# uController.net
KiCad netlist of a schematic drawn in Altium Designer
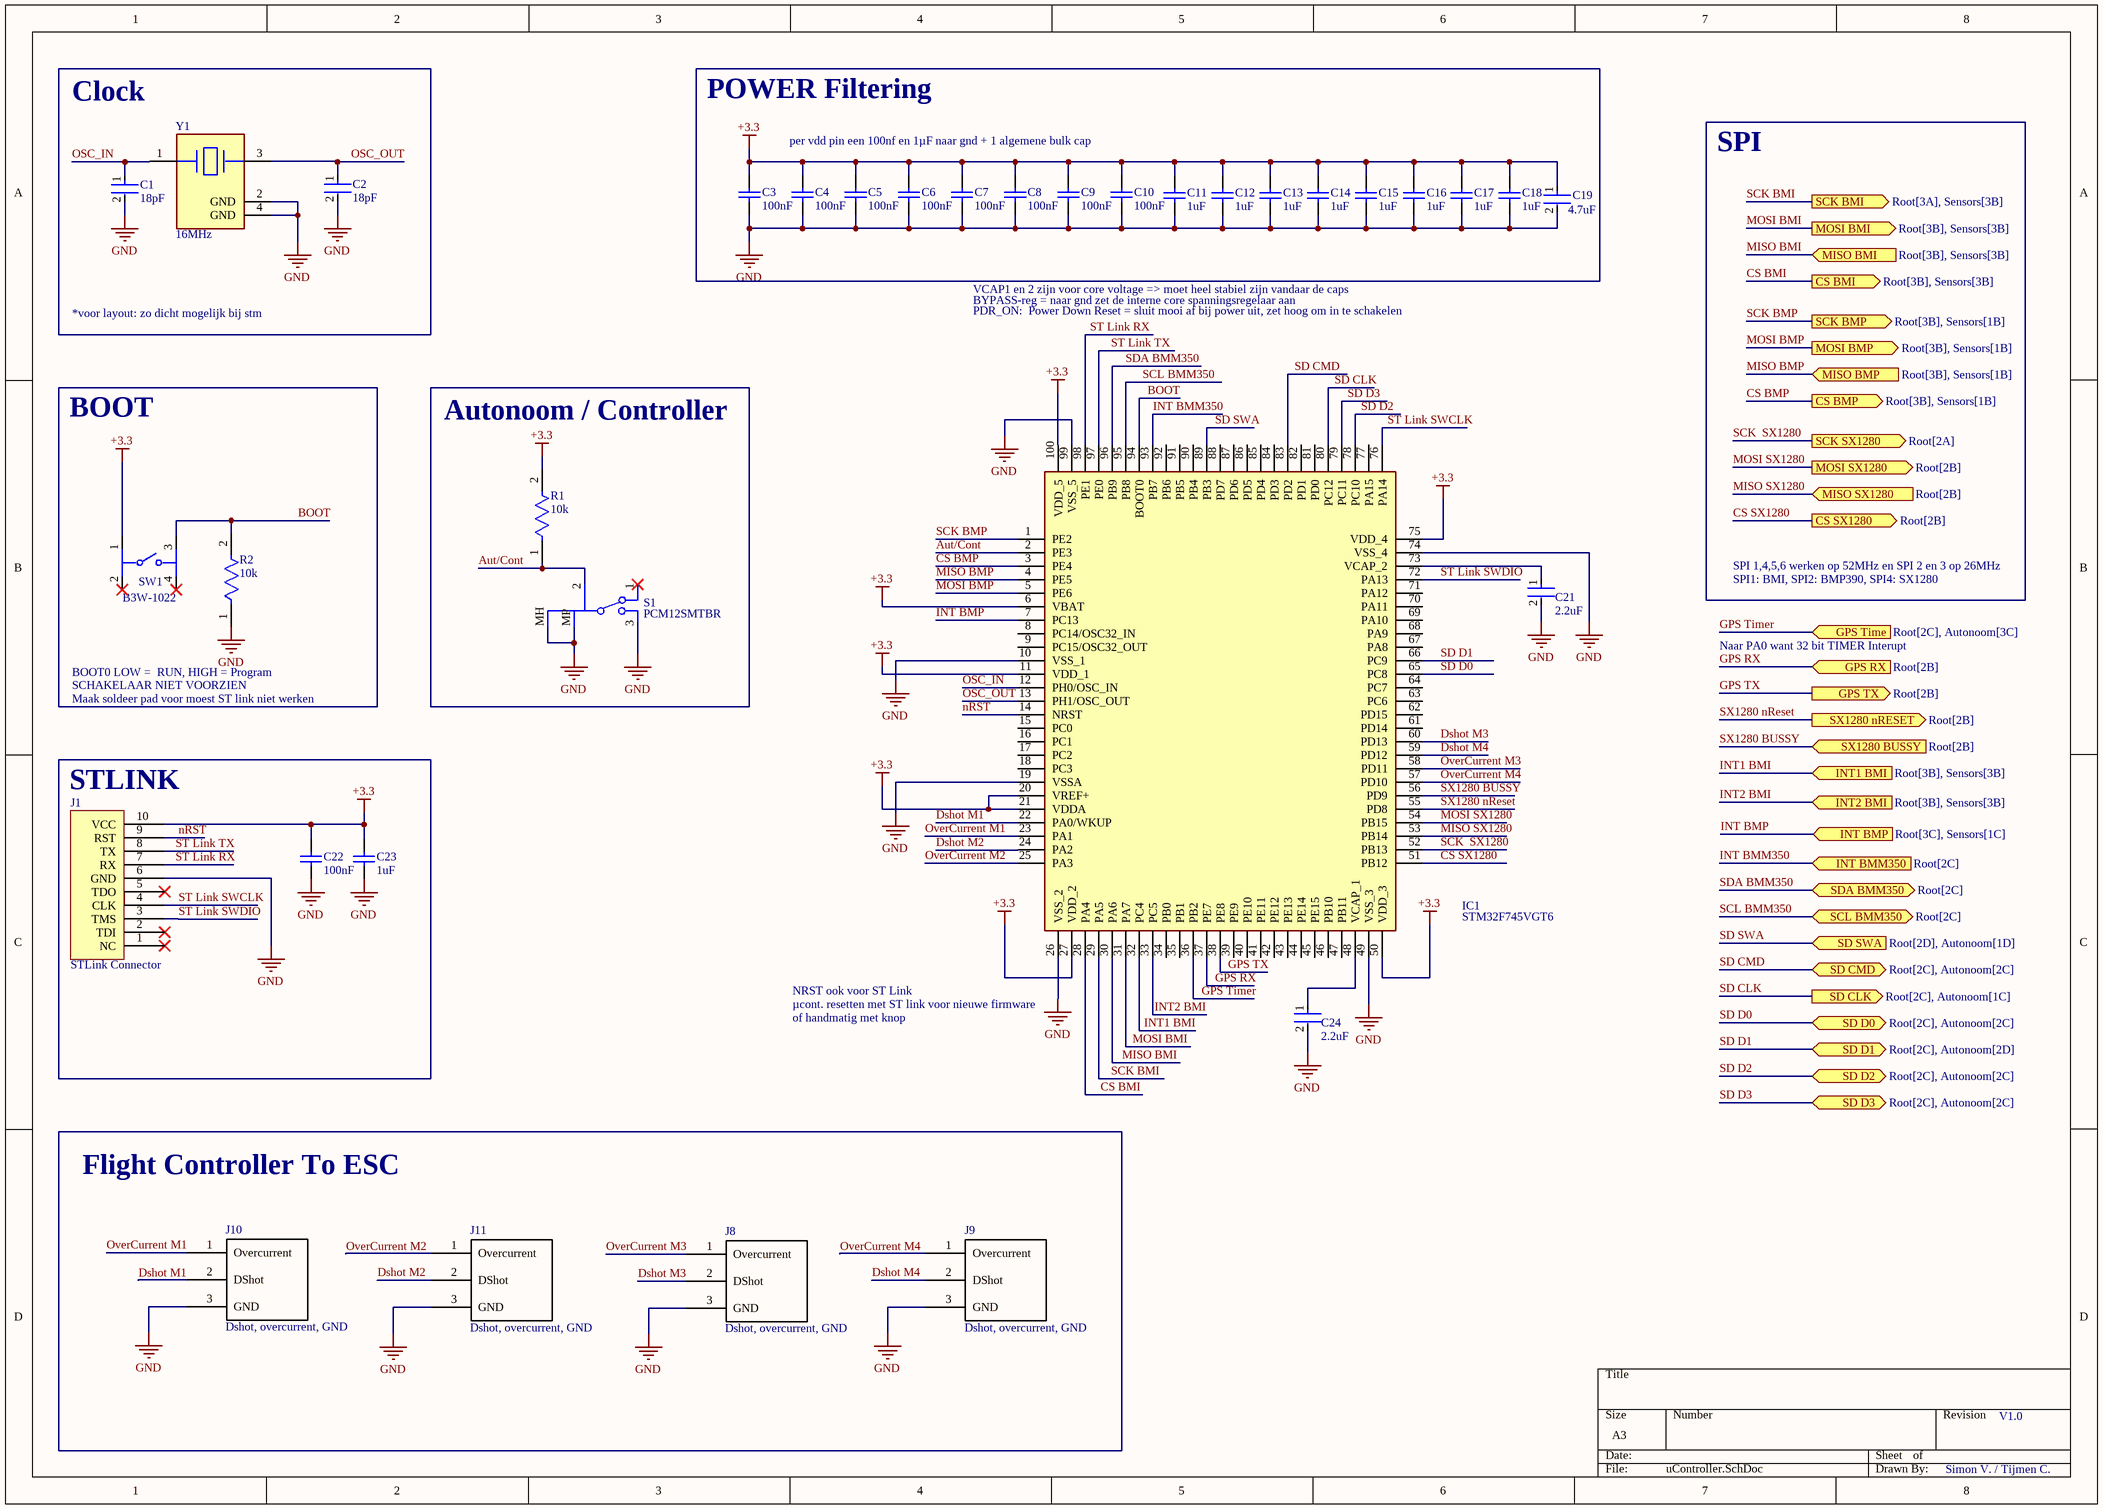
[diagram p0: uController.SchDoc]

(export (version "E")
  (design (tool "Eeschema 10.0.6"))
  (components
    (comp (ref "C1")
      (value "18pF")
      (footprint "FP-C0603C-CF-MFG")
      (description "C0603 18 pF C0G 30ppm/°C 1.00% 50 V")
      (fields
        (field (name "MANUFACTURER") "KEMET")
        (field (name "MANUFACTURER PART NUMBER") "C0603C180F5GACAUTO")
      )
      (libsource (lib "Altium Content Vault") (part "b4654b650e69147ec39a6b967a45e02"))
    )
    (comp (ref "C2")
      (value "18pF")
      (footprint "FP-C0603C-CF-MFG")
      (description "C0603 18 pF C0G 30ppm/°C 1.00% 50 V")
      (fields
        (field (name "MANUFACTURER") "KEMET")
        (field (name "MANUFACTURER PART NUMBER") "C0603C180F5GACAUTO")
      )
      (libsource (lib "Altium Content Vault") (part "b4654b650e69147ec39a6b967a45e02"))
    )
    (comp (ref "C3")
      (value "100nF")
      (footprint "CAPC1608X92X38ML15T08")
      (fields (field (name "PART NUMBER") "VJ0603Y104MXXAC") (field (name "MANUFACTURER") "Vitramon"))
      (libsource (lib "Altium Content Vault") (part "CAP"))
    )
    (comp (ref "C4")
      (value "100nF")
      (footprint "CAPC1608X92X38ML15T08")
      (fields (field (name "PART NUMBER") "VJ0603Y104MXXAC") (field (name "MANUFACTURER") "Vitramon"))
      (libsource (lib "Altium Content Vault") (part "CAP"))
    )
    (comp (ref "C5")
      (value "100nF")
      (footprint "CAPC1608X92X38ML15T08")
      (fields (field (name "PART NUMBER") "VJ0603Y104MXXAC") (field (name "MANUFACTURER") "Vitramon"))
      (libsource (lib "Altium Content Vault") (part "CAP"))
    )
    (comp (ref "C6")
      (value "100nF")
      (footprint "CAPC1608X92X38ML15T08")
      (fields (field (name "PART NUMBER") "VJ0603Y104MXXAC") (field (name "MANUFACTURER") "Vitramon"))
      (libsource (lib "Altium Content Vault") (part "CAP"))
    )
    (comp (ref "C7")
      (value "100nF")
      (footprint "CAPC1608X92X38ML15T08")
      (fields (field (name "PART NUMBER") "VJ0603Y104MXXAC") (field (name "MANUFACTURER") "Vitramon"))
      (libsource (lib "Altium Content Vault") (part "CAP"))
    )
    (comp (ref "C8")
      (value "100nF")
      (footprint "CAPC1608X92X38ML15T08")
      (fields (field (name "PART NUMBER") "VJ0603Y104MXXAC") (field (name "MANUFACTURER") "Vitramon"))
      (libsource (lib "Altium Content Vault") (part "CAP"))
    )
    (comp (ref "C9")
      (value "100nF")
      (footprint "CAPC1608X92X38ML15T08")
      (fields (field (name "PART NUMBER") "VJ0603Y104MXXAC") (field (name "MANUFACTURER") "Vitramon"))
      (libsource (lib "Altium Content Vault") (part "CAP"))
    )
    (comp (ref "C10")
      (value "100nF")
      (footprint "CAPC1608X92X38ML15T08")
      (fields (field (name "PART NUMBER") "VJ0603Y104MXXAC") (field (name "MANUFACTURER") "Vitramon"))
      (libsource (lib "Altium Content Vault") (part "CAP"))
    )
    (comp (ref "C11")
      (value "1uF")
      (footprint "CAPC1608X90X35NL15T15")
      (fields
        (field (name "PART NUMBER") "0603YD105MAT2A")
        (field (name "MANUFACTURER") "AVX Interconnect / Elco")
      )
      (libsource (lib "Altium Content Vault") (part "CAP"))
    )
    (comp (ref "C12")
      (value "1uF")
      (footprint "CAPC1608X90X35NL15T15")
      (fields
        (field (name "PART NUMBER") "0603YD105MAT2A")
        (field (name "MANUFACTURER") "AVX Interconnect / Elco")
      )
      (libsource (lib "Altium Content Vault") (part "CAP"))
    )
    (comp (ref "C13")
      (value "1uF")
      (footprint "CAPC1608X90X35NL15T15")
      (fields
        (field (name "PART NUMBER") "0603YD105MAT2A")
        (field (name "MANUFACTURER") "AVX Interconnect / Elco")
      )
      (libsource (lib "Altium Content Vault") (part "CAP"))
    )
    (comp (ref "C14")
      (value "1uF")
      (footprint "CAPC1608X90X35NL15T15")
      (fields
        (field (name "PART NUMBER") "0603YD105MAT2A")
        (field (name "MANUFACTURER") "AVX Interconnect / Elco")
      )
      (libsource (lib "Altium Content Vault") (part "CAP"))
    )
    (comp (ref "C15")
      (value "1uF")
      (footprint "CAPC1608X90X35NL15T15")
      (fields
        (field (name "PART NUMBER") "0603YD105MAT2A")
        (field (name "MANUFACTURER") "AVX Interconnect / Elco")
      )
      (libsource (lib "Altium Content Vault") (part "CAP"))
    )
    (comp (ref "C16")
      (value "1uF")
      (footprint "CAPC1608X90X35NL15T15")
      (fields
        (field (name "PART NUMBER") "0603YD105MAT2A")
        (field (name "MANUFACTURER") "AVX Interconnect / Elco")
      )
      (libsource (lib "Altium Content Vault") (part "CAP"))
    )
    (comp (ref "C17")
      (value "1uF")
      (footprint "CAPC1608X90X35NL15T15")
      (fields
        (field (name "PART NUMBER") "0603YD105MAT2A")
        (field (name "MANUFACTURER") "AVX Interconnect / Elco")
      )
      (libsource (lib "Altium Content Vault") (part "CAP"))
    )
    (comp (ref "C18")
      (value "1uF")
      (footprint "CAPC1608X90X35NL15T15")
      (fields
        (field (name "PART NUMBER") "0603YD105MAT2A")
        (field (name "MANUFACTURER") "AVX Interconnect / Elco")
      )
      (libsource (lib "Altium Content Vault") (part "CAP"))
    )
    (comp (ref "C19")
      (value "4.7uF")
      (footprint "FP-CC0603-DC-MFG")
      (description "CAP CER 4.7UF 6.3V X7R 0603")
      (fields (field (name "TOLERANCE") "20%"))
      (libsource (lib "Altium Content Vault") (part "11868f565c42a9108669ba33697ecf6"))
    )
    (comp (ref "C21")
      (value "2.2uF")
      (footprint "FP-CC0603-DA-MFG")
      (description "CC0603 2.2 uF X5R 10.00% 16 V")
      (fields
        (field (name "MANUFACTURER") "YAGEO")
        (field (name "MANUFACTURER PART NUMBER") "CC0603KPX5R7BB225")
      )
      (libsource (lib "Altium Content Vault") (part "11868f565c42a9108669ba33697ecf6"))
    )
    (comp (ref "C22")
      (value "100nF")
      (footprint "CAPC1608X92X38ML15T08")
      (fields (field (name "PART NUMBER") "VJ0603Y104MXXAC") (field (name "MANUFACTURER") "Vitramon"))
      (libsource (lib "Altium Content Vault") (part "CAP"))
    )
    (comp (ref "C23")
      (value "1uF")
      (footprint "CAPC1608X90X35NL15T15")
      (fields
        (field (name "PART NUMBER") "0603YD105MAT2A")
        (field (name "MANUFACTURER") "AVX Interconnect / Elco")
      )
      (libsource (lib "Altium Content Vault") (part "CAP"))
    )
    (comp (ref "C24")
      (value "2.2uF")
      (footprint "FP-CC0603-DA-MFG")
      (description "CC0603 2.2 uF X5R 10.00% 16 V")
      (fields
        (field (name "MANUFACTURER") "YAGEO")
        (field (name "MANUFACTURER PART NUMBER") "CC0603KPX5R7BB225")
      )
      (libsource (lib "Altium Content Vault") (part "11868f565c42a9108669ba33697ecf6"))
    )
    (comp (ref "IC1")
      (value "STM32F745VGT6")
      (footprint "SamacSys:QFP50P1600X1600X160-100N")
      (description "Integrated Circuit")
      (fields (field (name "MOUSER PART NUMBER") "511-STM32F745VGT6"))
      (libsource (lib "*") (part "STM32F745VGT6"))
    )
    (comp (ref "J1")
      (value "STLink Connector")
      (footprint "PCBComponent_1")
      (libsource (lib "stmpinconnector") (part "STLink Connector"))
    )
    (comp (ref "J8")
      (value "Dshot, overcurrent, GND")
      (footprint "FC-ESC_Connector")
      (libsource (lib "stmpinconnector (2)") (part "Dshot, overcurrent, GND"))
    )
    (comp (ref "J9")
      (value "Dshot, overcurrent, GND")
      (footprint "FC-ESC_Connector")
      (libsource (lib "stmpinconnector (2)") (part "Dshot, overcurrent, GND"))
    )
    (comp (ref "J10")
      (value "Dshot, overcurrent, GND")
      (footprint "FC-ESC_Connector")
      (libsource (lib "stmpinconnector (2)") (part "Dshot, overcurrent, GND"))
    )
    (comp (ref "J11")
      (value "Dshot, overcurrent, GND")
      (footprint "FC-ESC_Connector")
      (libsource (lib "stmpinconnector (2)") (part "Dshot, overcurrent, GND"))
    )
    (comp (ref "R1")
      (value "10k")
      (footprint "FP-MCT0603-MFG")
      (description "RES SMD 100 OHM 1% 1/8W 0603")
      (fields (field (name "TOLERANCE") "0.1%"))
      (libsource (lib "Altium Content Vault") (part "1029c3af85768c4190bb7ad29bc67b5"))
    )
    (comp (ref "R2")
      (value "10k")
      (footprint "FP-MCT0603-MFG")
      (description "RES SMD 100 OHM 1% 1/8W 0603")
      (fields (field (name "TOLERANCE") "0.1%"))
      (libsource (lib "Altium Content Vault") (part "1029c3af85768c4190bb7ad29bc67b5"))
    )
    (comp (ref "S1")
      (value "PCM12SMTBR")
      (footprint "PCM12SMTBR")
      (libsource (lib "PCM12SMTBR") (part "PCM12SMTBR"))
    )
    (comp (ref "SW1")
      (value "B3W-1022")
      (footprint "FP-B3W-1022-MFG")
      (description "SWITCH TACTILE SPST-NO 0.05A 24V")
      (libsource (lib "Altium Content Vault") (part "b8895f3f4cefb76e1819d2863dba89b"))
    )
    (comp (ref "Y1")
      (value "16MHz")
      (footprint "FP-ABM8-MFG")
      (description "Crystal 16MHz ±20ppm 18pF SMD-4 3.2mm x 2.5mm                      ABM8-16.000MHZ-B2-T3")
      (libsource (lib "Altium Content Vault") (part "dfdb7f9a12507849fb681da9a70121c"))
    )
  )
  (nets
    (net (code "1") (name "+3.3") (class "Default")
      (node (ref "C10") (pin "2") (pinfunction "2_2") (pintype "passive"))
      (node (ref "C11") (pin "2") (pinfunction "2_2") (pintype "passive"))
      (node (ref "C12") (pin "2") (pinfunction "2_2") (pintype "passive"))
      (node (ref "C13") (pin "2") (pinfunction "2_2") (pintype "passive"))
      (node (ref "C14") (pin "2") (pinfunction "2_2") (pintype "passive"))
      (node (ref "C15") (pin "2") (pinfunction "2_2") (pintype "passive"))
      (node (ref "C16") (pin "2") (pinfunction "2_2") (pintype "passive"))
      (node (ref "C17") (pin "2") (pinfunction "2_2") (pintype "passive"))
      (node (ref "C18") (pin "2") (pinfunction "2_2") (pintype "passive"))
      (node (ref "C19") (pin "1") (pinfunction "1_1") (pintype "passive"))
      (node (ref "C22") (pin "2") (pinfunction "2_2") (pintype "passive"))
      (node (ref "C23") (pin "2") (pinfunction "2_2") (pintype "passive"))
      (node (ref "C3") (pin "2") (pinfunction "2_2") (pintype "passive"))
      (node (ref "C4") (pin "2") (pinfunction "2_2") (pintype "passive"))
      (node (ref "C5") (pin "2") (pinfunction "2_2") (pintype "passive"))
      (node (ref "C6") (pin "2") (pinfunction "2_2") (pintype "passive"))
      (node (ref "C7") (pin "2") (pinfunction "2_2") (pintype "passive"))
      (node (ref "C8") (pin "2") (pinfunction "2_2") (pintype "passive"))
      (node (ref "C9") (pin "2") (pinfunction "2_2") (pintype "passive"))
      (node (ref "IC1") (pin "100") (pinfunction "VDD_5_100") (pintype "power_in"))
      (node (ref "IC1") (pin "11") (pinfunction "VDD_1_11") (pintype "power_in"))
      (node (ref "IC1") (pin "20") (pinfunction "VREF+_20") (pintype "power_in"))
      (node (ref "IC1") (pin "21") (pinfunction "VDDA_21") (pintype "power_in"))
      (node (ref "IC1") (pin "27") (pinfunction "VDD_2_27") (pintype "power_in"))
      (node (ref "IC1") (pin "50") (pinfunction "VDD_3_50") (pintype "power_in"))
      (node (ref "IC1") (pin "6") (pinfunction "VBAT_6") (pintype "power_in"))
      (node (ref "IC1") (pin "75") (pinfunction "VDD_4_75") (pintype "power_in"))
      (node (ref "J1") (pin "10") (pinfunction "VCC_10") (pintype "passive"))
      (node (ref "R1") (pin "2") (pinfunction "2_2") (pintype "passive"))
      (node (ref "SW1") (pin "1") (pinfunction "1_1") (pintype "passive"))
    )
    (net (code "2") (name "/Aut{slash}Cont") (class "Default")
      (node (ref "IC1") (pin "2") (pinfunction "PE3_2") (pintype "passive"))
      (node (ref "R1") (pin "1") (pinfunction "1_1") (pintype "passive"))
      (node (ref "S1") (pin "2") (pinfunction "2_2") (pintype "passive"))
    )
    (net (code "3") (name "/BOOT") (class "Default")
      (node (ref "IC1") (pin "94") (pinfunction "BOOT0_94") (pintype "passive"))
      (node (ref "R2") (pin "2") (pinfunction "2_2") (pintype "passive"))
      (node (ref "SW1") (pin "3") (pinfunction "3_3") (pintype "passive"))
    )
    (net (code "4") (name "/CS BMI") (class "Default")
      (node (ref "IC1") (pin "28") (pinfunction "PA4_28") (pintype "passive"))
    )
    (net (code "5") (name "/CS BMP") (class "Default")
      (node (ref "IC1") (pin "3") (pinfunction "PE4_3") (pintype "passive"))
    )
    (net (code "6") (name "/CS SX1280") (class "Default")
      (node (ref "IC1") (pin "51") (pinfunction "PB12_51") (pintype "passive"))
    )
    (net (code "7") (name "/Dshot M1") (class "Default")
      (node (ref "IC1") (pin "22") (pinfunction "PA0/WKUP_22") (pintype "passive"))
      (node (ref "J10") (pin "2") (pinfunction "DShot_2") (pintype "passive"))
    )
    (net (code "8") (name "/Dshot M2") (class "Default")
      (node (ref "IC1") (pin "24") (pinfunction "PA2_24") (pintype "passive"))
      (node (ref "J11") (pin "2") (pinfunction "DShot_2") (pintype "passive"))
    )
    (net (code "9") (name "/Dshot M3") (class "Default")
      (node (ref "IC1") (pin "60") (pinfunction "PD13_60") (pintype "passive"))
      (node (ref "J8") (pin "2") (pinfunction "DShot_2") (pintype "passive"))
    )
    (net (code "10") (name "/Dshot M4") (class "Default")
      (node (ref "IC1") (pin "59") (pinfunction "PD12_59") (pintype "passive"))
      (node (ref "J9") (pin "2") (pinfunction "DShot_2") (pintype "passive"))
    )
    (net (code "11") (name "/GPS RX") (class "Default")
      (node (ref "IC1") (pin "37") (pinfunction "PE7_37") (pintype "passive"))
    )
    (net (code "12") (name "/GPS TX") (class "Default")
      (node (ref "IC1") (pin "38") (pinfunction "PE8_38") (pintype "passive"))
    )
    (net (code "13") (name "/GPS Timer") (class "Default")
      (node (ref "IC1") (pin "36") (pinfunction "PB2_36") (pintype "passive"))
    )
    (net (code "14") (name "/INT BMM350") (class "Default")
      (node (ref "IC1") (pin "93") (pinfunction "PB7_93") (pintype "passive"))
    )
    (net (code "15") (name "/INT BMP") (class "Default")
      (node (ref "IC1") (pin "7") (pinfunction "PC13_7") (pintype "passive"))
    )
    (net (code "16") (name "/INT1 BMI") (class "Default")
      (node (ref "IC1") (pin "32") (pinfunction "PC4_32") (pintype "passive"))
    )
    (net (code "17") (name "/INT2 BMI") (class "Default")
      (node (ref "IC1") (pin "33") (pinfunction "PC5_33") (pintype "passive"))
    )
    (net (code "18") (name "/MISO BMI") (class "Default")
      (node (ref "IC1") (pin "30") (pinfunction "PA6_30") (pintype "passive"))
    )
    (net (code "19") (name "/MISO BMP") (class "Default")
      (node (ref "IC1") (pin "4") (pinfunction "PE5_4") (pintype "passive"))
    )
    (net (code "20") (name "/MISO SX1280") (class "Default")
      (node (ref "IC1") (pin "53") (pinfunction "PB14_53") (pintype "passive"))
    )
    (net (code "21") (name "/MOSI BMI") (class "Default")
      (node (ref "IC1") (pin "31") (pinfunction "PA7_31") (pintype "passive"))
    )
    (net (code "22") (name "/MOSI BMP") (class "Default")
      (node (ref "IC1") (pin "5") (pinfunction "PE6_5") (pintype "passive"))
    )
    (net (code "23") (name "/MOSI SX1280") (class "Default")
      (node (ref "IC1") (pin "54") (pinfunction "PB15_54") (pintype "passive"))
    )
    (net (code "24") (name "/OSC_IN") (class "Default")
      (node (ref "C1") (pin "1") (pinfunction "1_1") (pintype "passive"))
      (node (ref "IC1") (pin "12") (pinfunction "PH0/OSC_IN_12") (pintype "passive"))
      (node (ref "Y1") (pin "1") (pinfunction "1_1") (pintype "passive"))
    )
    (net (code "25") (name "/OSC_OUT") (class "Default")
      (node (ref "C2") (pin "1") (pinfunction "1_1") (pintype "passive"))
      (node (ref "IC1") (pin "13") (pinfunction "PH1/OSC_OUT_13") (pintype "passive"))
      (node (ref "Y1") (pin "3") (pinfunction "3_3") (pintype "passive"))
    )
    (net (code "26") (name "/OverCurrent M1") (class "Default")
      (node (ref "IC1") (pin "23") (pinfunction "PA1_23") (pintype "passive"))
      (node (ref "J10") (pin "1") (pinfunction "Overcurrent_1") (pintype "passive"))
    )
    (net (code "27") (name "/OverCurrent M2") (class "Default")
      (node (ref "IC1") (pin "25") (pinfunction "PA3_25") (pintype "passive"))
      (node (ref "J11") (pin "1") (pinfunction "Overcurrent_1") (pintype "passive"))
    )
    (net (code "28") (name "/OverCurrent M3") (class "Default")
      (node (ref "IC1") (pin "58") (pinfunction "PD11_58") (pintype "passive"))
      (node (ref "J8") (pin "1") (pinfunction "Overcurrent_1") (pintype "passive"))
    )
    (net (code "29") (name "/OverCurrent M4") (class "Default")
      (node (ref "IC1") (pin "57") (pinfunction "PD10_57") (pintype "passive"))
      (node (ref "J9") (pin "1") (pinfunction "Overcurrent_1") (pintype "passive"))
    )
    (net (code "30") (name "/SCK  SX1280") (class "Default")
      (node (ref "IC1") (pin "52") (pinfunction "PB13_52") (pintype "passive"))
    )
    (net (code "31") (name "/SCK BMI") (class "Default")
      (node (ref "IC1") (pin "29") (pinfunction "PA5_29") (pintype "passive"))
    )
    (net (code "32") (name "/SCK BMP") (class "Default")
      (node (ref "IC1") (pin "1") (pinfunction "PE2_1") (pintype "passive"))
    )
    (net (code "33") (name "/SCL BMM350") (class "Default")
      (node (ref "IC1") (pin "95") (pinfunction "PB8_95") (pintype "passive"))
    )
    (net (code "34") (name "/SD CLK") (class "Default")
      (node (ref "IC1") (pin "80") (pinfunction "PC12_80") (pintype "passive"))
    )
    (net (code "35") (name "/SD CMD") (class "Default")
      (node (ref "IC1") (pin "83") (pinfunction "PD2_83") (pintype "passive"))
    )
    (net (code "36") (name "/SD D0") (class "Default")
      (node (ref "IC1") (pin "65") (pinfunction "PC8_65") (pintype "passive"))
    )
    (net (code "37") (name "/SD D1") (class "Default")
      (node (ref "IC1") (pin "66") (pinfunction "PC9_66") (pintype "passive"))
    )
    (net (code "38") (name "/SD D2") (class "Default")
      (node (ref "IC1") (pin "78") (pinfunction "PC10_78") (pintype "passive"))
    )
    (net (code "39") (name "/SD D3") (class "Default")
      (node (ref "IC1") (pin "79") (pinfunction "PC11_79") (pintype "passive"))
    )
    (net (code "40") (name "/SD SWA") (class "Default")
      (node (ref "IC1") (pin "89") (pinfunction "PB3_89") (pintype "passive"))
    )
    (net (code "41") (name "/SDA BMM350") (class "Default")
      (node (ref "IC1") (pin "96") (pinfunction "PB9_96") (pintype "passive"))
    )
    (net (code "42") (name "/ST Link RX") (class "Default")
      (node (ref "IC1") (pin "98") (pinfunction "PE1_98") (pintype "passive"))
      (node (ref "J1") (pin "7") (pinfunction "RX_7") (pintype "passive"))
    )
    (net (code "43") (name "/ST Link SWCLK") (class "Default")
      (node (ref "IC1") (pin "76") (pinfunction "PA14_76") (pintype "passive"))
      (node (ref "J1") (pin "4") (pinfunction "CLK_4") (pintype "passive"))
    )
    (net (code "44") (name "/ST Link SWDIO") (class "Default")
      (node (ref "IC1") (pin "72") (pinfunction "PA13_72") (pintype "passive"))
      (node (ref "J1") (pin "3") (pinfunction "TMS_3") (pintype "passive"))
    )
    (net (code "45") (name "/ST Link TX") (class "Default")
      (node (ref "IC1") (pin "97") (pinfunction "PE0_97") (pintype "passive"))
      (node (ref "J1") (pin "8") (pinfunction "TX_8") (pintype "passive"))
    )
    (net (code "46") (name "/SX1280 BUSSY") (class "Default")
      (node (ref "IC1") (pin "56") (pinfunction "PD9_56") (pintype "passive"))
    )
    (net (code "47") (name "/SX1280 nReset") (class "Default")
      (node (ref "IC1") (pin "55") (pinfunction "PD8_55") (pintype "passive"))
    )
    (net (code "48") (name "/nRST") (class "Default")
      (node (ref "IC1") (pin "14") (pinfunction "NRST_14") (pintype "passive"))
      (node (ref "J1") (pin "9") (pinfunction "RST_9") (pintype "passive"))
    )
    (net (code "49") (name "GND") (class "Default")
      (node (ref "C1") (pin "2") (pinfunction "2_2") (pintype "passive"))
      (node (ref "C10") (pin "1") (pinfunction "1_1") (pintype "passive"))
      (node (ref "C11") (pin "1") (pinfunction "1_1") (pintype "passive"))
      (node (ref "C12") (pin "1") (pinfunction "1_1") (pintype "passive"))
      (node (ref "C13") (pin "1") (pinfunction "1_1") (pintype "passive"))
      (node (ref "C14") (pin "1") (pinfunction "1_1") (pintype "passive"))
      (node (ref "C15") (pin "1") (pinfunction "1_1") (pintype "passive"))
      (node (ref "C16") (pin "1") (pinfunction "1_1") (pintype "passive"))
      (node (ref "C17") (pin "1") (pinfunction "1_1") (pintype "passive"))
      (node (ref "C18") (pin "1") (pinfunction "1_1") (pintype "passive"))
      (node (ref "C19") (pin "2") (pinfunction "2_2") (pintype "passive"))
      (node (ref "C2") (pin "2") (pinfunction "2_2") (pintype "passive"))
      (node (ref "C21") (pin "2") (pinfunction "2_2") (pintype "passive"))
      (node (ref "C22") (pin "1") (pinfunction "1_1") (pintype "passive"))
      (node (ref "C23") (pin "1") (pinfunction "1_1") (pintype "passive"))
      (node (ref "C24") (pin "2") (pinfunction "2_2") (pintype "passive"))
      (node (ref "C3") (pin "1") (pinfunction "1_1") (pintype "passive"))
      (node (ref "C4") (pin "1") (pinfunction "1_1") (pintype "passive"))
      (node (ref "C5") (pin "1") (pinfunction "1_1") (pintype "passive"))
      (node (ref "C6") (pin "1") (pinfunction "1_1") (pintype "passive"))
      (node (ref "C7") (pin "1") (pinfunction "1_1") (pintype "passive"))
      (node (ref "C8") (pin "1") (pinfunction "1_1") (pintype "passive"))
      (node (ref "C9") (pin "1") (pinfunction "1_1") (pintype "passive"))
      (node (ref "IC1") (pin "10") (pinfunction "VSS_1_10") (pintype "power_in"))
      (node (ref "IC1") (pin "19") (pinfunction "VSSA_19") (pintype "power_in"))
      (node (ref "IC1") (pin "26") (pinfunction "VSS_2_26") (pintype "power_in"))
      (node (ref "IC1") (pin "49") (pinfunction "VSS_3_49") (pintype "power_in"))
      (node (ref "IC1") (pin "74") (pinfunction "VSS_4_74") (pintype "power_in"))
      (node (ref "IC1") (pin "99") (pinfunction "VSS_5_99") (pintype "power_in"))
      (node (ref "J1") (pin "6") (pinfunction "GND_6") (pintype "passive"))
      (node (ref "J10") (pin "3") (pinfunction "GND_3") (pintype "passive"))
      (node (ref "J11") (pin "3") (pinfunction "GND_3") (pintype "passive"))
      (node (ref "J8") (pin "3") (pinfunction "GND_3") (pintype "passive"))
      (node (ref "J9") (pin "3") (pinfunction "GND_3") (pintype "passive"))
      (node (ref "R2") (pin "1") (pinfunction "1_1") (pintype "passive"))
      (node (ref "S1") (pin "3") (pinfunction "3_3") (pintype "passive"))
      (node (ref "S1") (pin "MH") (pinfunction "MP_MH") (pintype "passive"))
      (node (ref "S1") (pin "MP") (pinfunction "5_MP") (pintype "passive"))
      (node (ref "Y1") (pin "2") (pinfunction "GND_2") (pintype "power_in"))
      (node (ref "Y1") (pin "4") (pinfunction "GND_4") (pintype "power_in"))
    )
    (net (code "50") (name "Net-(IC1-VCAP_1)") (class "Default")
      (node (ref "C24") (pin "1") (pinfunction "1_1") (pintype "passive"))
      (node (ref "IC1") (pin "48") (pinfunction "VCAP_1_48") (pintype "power_in"))
    )
    (net (code "51") (name "Net-(IC1-VCAP_2)") (class "Default")
      (node (ref "C21") (pin "1") (pinfunction "1_1") (pintype "passive"))
      (node (ref "IC1") (pin "73") (pinfunction "VCAP_2_73") (pintype "power_in"))
    )
    (net (code "52") (name "unconnected-(IC1-PA8-Pad67)") (class "Default")
      (node (ref "IC1") (pin "67") (pinfunction "PA8_67") (pintype "passive"))
    )
    (net (code "53") (name "unconnected-(IC1-PA9-Pad68)") (class "Default")
      (node (ref "IC1") (pin "68") (pinfunction "PA9_68") (pintype "passive"))
    )
    (net (code "54") (name "unconnected-(IC1-PA10-Pad69)") (class "Default")
      (node (ref "IC1") (pin "69") (pinfunction "PA10_69") (pintype "passive"))
    )
    (net (code "55") (name "unconnected-(IC1-PA11-Pad70)") (class "Default")
      (node (ref "IC1") (pin "70") (pinfunction "PA11_70") (pintype "passive"))
    )
    (net (code "56") (name "unconnected-(IC1-PA12-Pad71)") (class "Default")
      (node (ref "IC1") (pin "71") (pinfunction "PA12_71") (pintype "passive"))
    )
    (net (code "57") (name "unconnected-(IC1-PA15-Pad77)") (class "Default")
      (node (ref "IC1") (pin "77") (pinfunction "PA15_77") (pintype "passive"))
    )
    (net (code "58") (name "unconnected-(IC1-PB0-Pad34)") (class "Default")
      (node (ref "IC1") (pin "34") (pinfunction "PB0_34") (pintype "passive"))
    )
    (net (code "59") (name "unconnected-(IC1-PB1-Pad35)") (class "Default")
      (node (ref "IC1") (pin "35") (pinfunction "PB1_35") (pintype "passive"))
    )
    (net (code "60") (name "unconnected-(IC1-PB4-Pad90)") (class "Default")
      (node (ref "IC1") (pin "90") (pinfunction "PB4_90") (pintype "passive"))
    )
    (net (code "61") (name "unconnected-(IC1-PB5-Pad91)") (class "Default")
      (node (ref "IC1") (pin "91") (pinfunction "PB5_91") (pintype "passive"))
    )
    (net (code "62") (name "unconnected-(IC1-PB6-Pad92)") (class "Default")
      (node (ref "IC1") (pin "92") (pinfunction "PB6_92") (pintype "passive"))
    )
    (net (code "63") (name "unconnected-(IC1-PB10-Pad46)") (class "Default")
      (node (ref "IC1") (pin "46") (pinfunction "PB10_46") (pintype "passive"))
    )
    (net (code "64") (name "unconnected-(IC1-PB11-Pad47)") (class "Default")
      (node (ref "IC1") (pin "47") (pinfunction "PB11_47") (pintype "passive"))
    )
    (net (code "65") (name "unconnected-(IC1-PC0-Pad15)") (class "Default")
      (node (ref "IC1") (pin "15") (pinfunction "PC0_15") (pintype "passive"))
    )
    (net (code "66") (name "unconnected-(IC1-PC1-Pad16)") (class "Default")
      (node (ref "IC1") (pin "16") (pinfunction "PC1_16") (pintype "passive"))
    )
    (net (code "67") (name "unconnected-(IC1-PC2-Pad17)") (class "Default")
      (node (ref "IC1") (pin "17") (pinfunction "PC2_17") (pintype "passive"))
    )
    (net (code "68") (name "unconnected-(IC1-PC3-Pad18)") (class "Default")
      (node (ref "IC1") (pin "18") (pinfunction "PC3_18") (pintype "passive"))
    )
    (net (code "69") (name "unconnected-(IC1-PC6-Pad63)") (class "Default")
      (node (ref "IC1") (pin "63") (pinfunction "PC6_63") (pintype "passive"))
    )
    (net (code "70") (name "unconnected-(IC1-PC7-Pad64)") (class "Default")
      (node (ref "IC1") (pin "64") (pinfunction "PC7_64") (pintype "passive"))
    )
    (net (code "71") (name "unconnected-(IC1-PC14{slash}OSC32_IN-Pad8)") (class "Default")
      (node (ref "IC1") (pin "8") (pinfunction "PC14/OSC32_IN_8") (pintype "passive"))
    )
    (net (code "72") (name "unconnected-(IC1-PC15{slash}OSC32_OUT-Pad9)") (class "Default")
      (node (ref "IC1") (pin "9") (pinfunction "PC15/OSC32_OUT_9") (pintype "passive"))
    )
    (net (code "73") (name "unconnected-(IC1-PD0-Pad81)") (class "Default")
      (node (ref "IC1") (pin "81") (pinfunction "PD0_81") (pintype "passive"))
    )
    (net (code "74") (name "unconnected-(IC1-PD1-Pad82)") (class "Default")
      (node (ref "IC1") (pin "82") (pinfunction "PD1_82") (pintype "passive"))
    )
    (net (code "75") (name "unconnected-(IC1-PD3-Pad84)") (class "Default")
      (node (ref "IC1") (pin "84") (pinfunction "PD3_84") (pintype "passive"))
    )
    (net (code "76") (name "unconnected-(IC1-PD4-Pad85)") (class "Default")
      (node (ref "IC1") (pin "85") (pinfunction "PD4_85") (pintype "passive"))
    )
    (net (code "77") (name "unconnected-(IC1-PD5-Pad86)") (class "Default")
      (node (ref "IC1") (pin "86") (pinfunction "PD5_86") (pintype "passive"))
    )
    (net (code "78") (name "unconnected-(IC1-PD6-Pad87)") (class "Default")
      (node (ref "IC1") (pin "87") (pinfunction "PD6_87") (pintype "passive"))
    )
    (net (code "79") (name "unconnected-(IC1-PD7-Pad88)") (class "Default")
      (node (ref "IC1") (pin "88") (pinfunction "PD7_88") (pintype "passive"))
    )
    (net (code "80") (name "unconnected-(IC1-PD14-Pad61)") (class "Default")
      (node (ref "IC1") (pin "61") (pinfunction "PD14_61") (pintype "passive"))
    )
    (net (code "81") (name "unconnected-(IC1-PD15-Pad62)") (class "Default")
      (node (ref "IC1") (pin "62") (pinfunction "PD15_62") (pintype "passive"))
    )
    (net (code "82") (name "unconnected-(IC1-PE9-Pad39)") (class "Default")
      (node (ref "IC1") (pin "39") (pinfunction "PE9_39") (pintype "passive"))
    )
    (net (code "83") (name "unconnected-(IC1-PE10-Pad40)") (class "Default")
      (node (ref "IC1") (pin "40") (pinfunction "PE10_40") (pintype "passive"))
    )
    (net (code "84") (name "unconnected-(IC1-PE11-Pad41)") (class "Default")
      (node (ref "IC1") (pin "41") (pinfunction "PE11_41") (pintype "passive"))
    )
    (net (code "85") (name "unconnected-(IC1-PE12-Pad42)") (class "Default")
      (node (ref "IC1") (pin "42") (pinfunction "PE12_42") (pintype "passive"))
    )
    (net (code "86") (name "unconnected-(IC1-PE13-Pad43)") (class "Default")
      (node (ref "IC1") (pin "43") (pinfunction "PE13_43") (pintype "passive"))
    )
    (net (code "87") (name "unconnected-(IC1-PE14-Pad44)") (class "Default")
      (node (ref "IC1") (pin "44") (pinfunction "PE14_44") (pintype "passive"))
    )
    (net (code "88") (name "unconnected-(IC1-PE15-Pad45)") (class "Default")
      (node (ref "IC1") (pin "45") (pinfunction "PE15_45") (pintype "passive"))
    )
    (net (code "89") (name "unconnected-(J1-NC-Pad1)") (class "Default")
      (node (ref "J1") (pin "1") (pinfunction "NC_1") (pintype "passive+no_connect"))
    )
    (net (code "90") (name "unconnected-(J1-TDI-Pad2)") (class "Default")
      (node (ref "J1") (pin "2") (pinfunction "TDI_2") (pintype "passive+no_connect"))
    )
    (net (code "91") (name "unconnected-(J1-TDO-Pad5)") (class "Default")
      (node (ref "J1") (pin "5") (pinfunction "TDO_5") (pintype "passive+no_connect"))
    )
    (net (code "92") (name "unconnected-(S1-Pad1)") (class "Default")
      (node (ref "S1") (pin "1") (pinfunction "1_1") (pintype "passive+no_connect"))
    )
    (net (code "93") (name "unconnected-(SW1-Pad2)") (class "Default")
      (node (ref "SW1") (pin "2") (pinfunction "2_2") (pintype "passive+no_connect"))
    )
    (net (code "94") (name "unconnected-(SW1-Pad4)") (class "Default")
      (node (ref "SW1") (pin "4") (pinfunction "4_4") (pintype "passive+no_connect"))
    )
  )
)
